# RGBstrip-ESP07-Controller-Amp.net
KiCad netlist of a schematic drawn in EAGLE
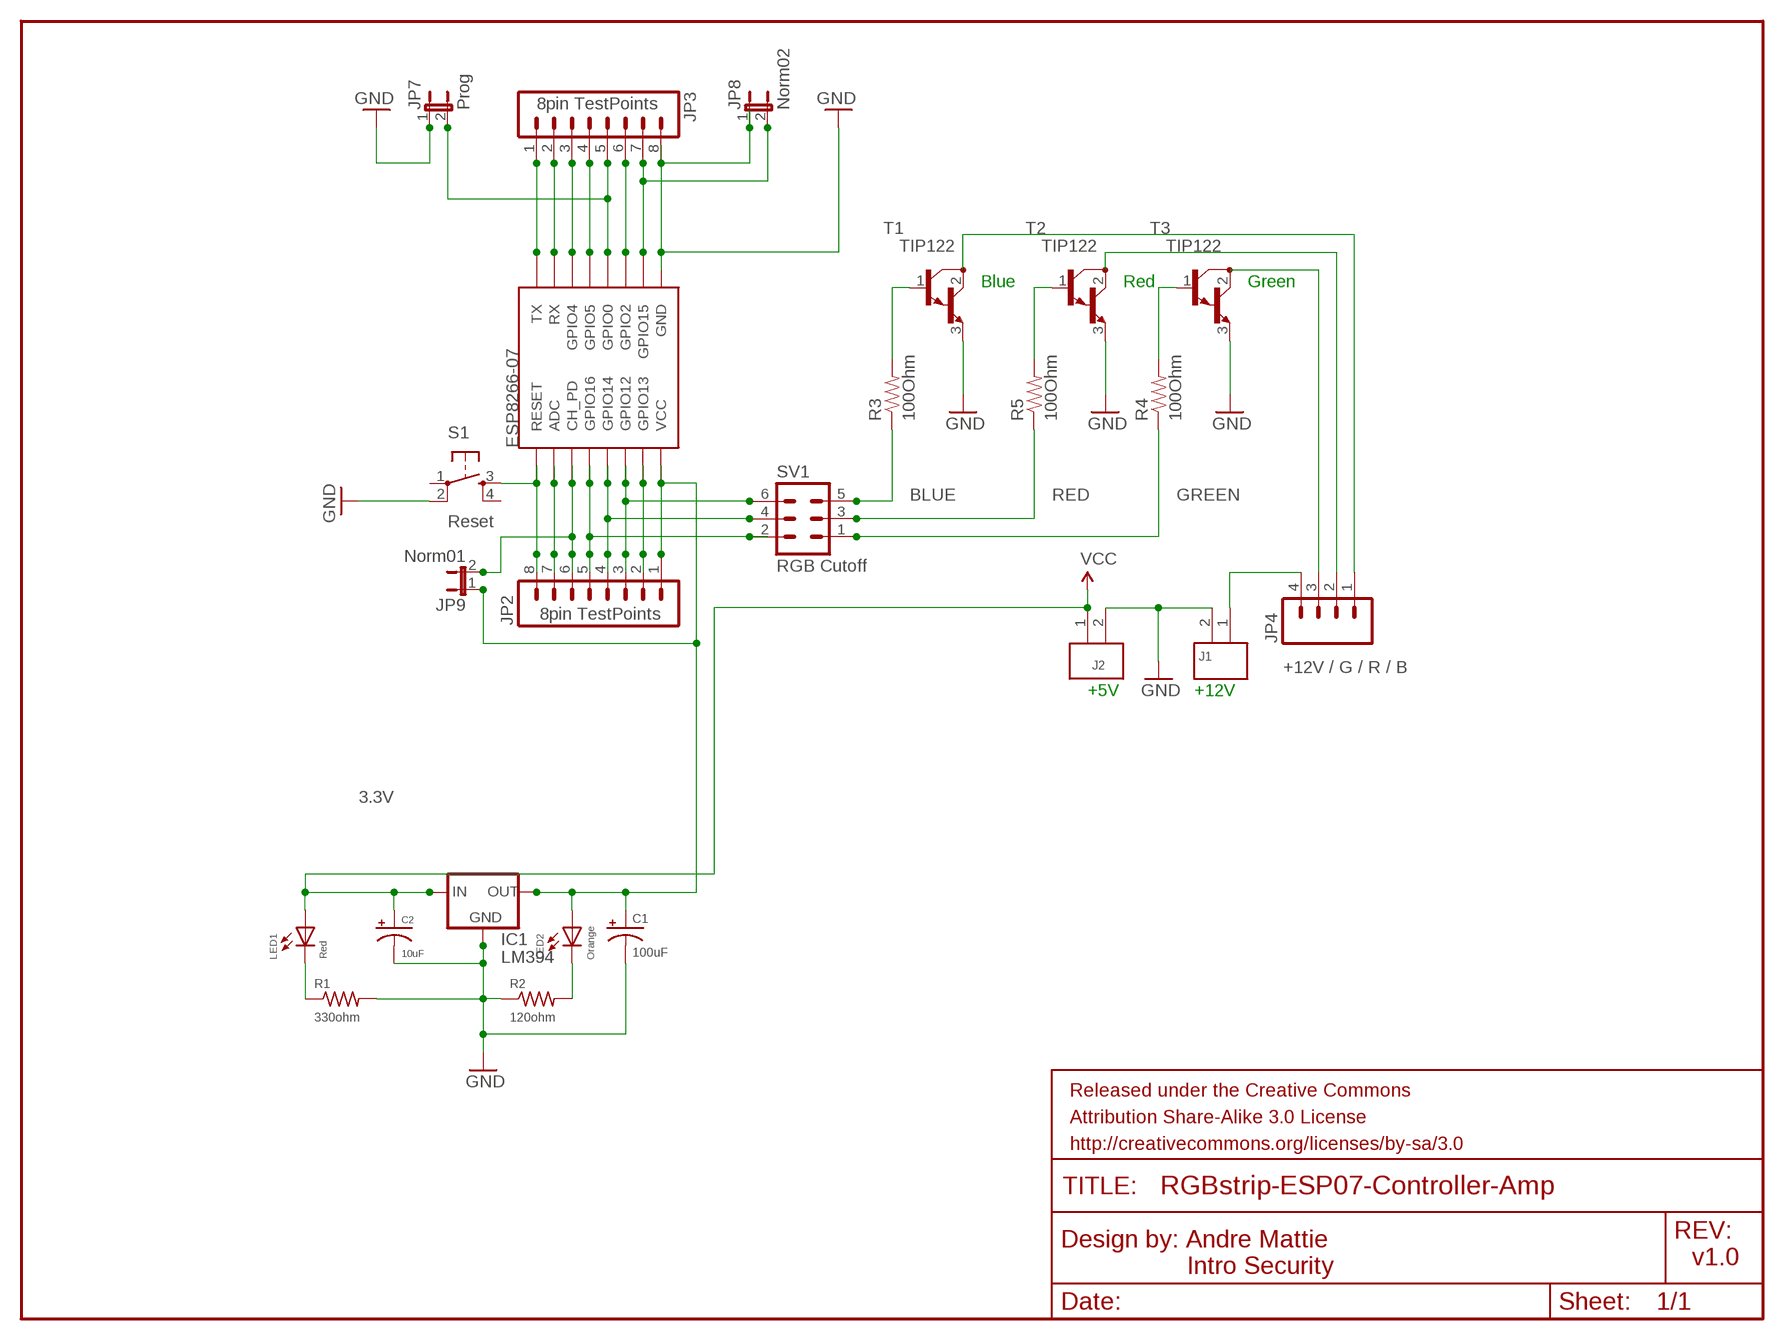
[diagram p0: schematic, sheet 1]

(export (version "E")
  (design (tool "Eeschema 10.0.6"))
  (components
    (comp (ref "C1")
      (value "100uF")
      (footprint "eagle-import:CPOL-RADIAL-100UF-25V")
      (libsource (lib "eagle-import") (part "CAP_POLPTH1"))
    )
    (comp (ref "C2")
      (value "10uF")
      (footprint "eagle-import:CPOL-RADIAL-10UF-25V")
      (libsource (lib "eagle-import") (part "CAP_POLPTH2"))
    )
    (comp (ref "ESP8266-07")
      (value "ESP07-16PIN")
      (footprint "eagle-import:ESP07-16PIN")
      (libsource (lib "eagle-import") (part "ESP07-16PIN"))
    )
    (comp (ref "FRAME1")
      (value "FRAME-LETTER")
      (footprint "eagle-import:CREATIVE_COMMONS")
      (libsource (lib "eagle-import") (part "FRAME-LETTER"))
    )
    (comp (ref "IC1")
      (value "LM394")
      (footprint "eagle-import:TO220-IGO")
      (libsource (lib "eagle-import") (part "V_REG_78XXSINK"))
    )
    (comp (ref "J1")
      (value "SCREW-TERMINAL_2_0.100")
      (footprint "eagle-import:CONN_BLOCK_2")
      (libsource (lib "eagle-import") (part "SCREW-TERMINAL_2_0.100"))
    )
    (comp (ref "J2")
      (value "SCREW-TERMINAL_2_0.100")
      (footprint "eagle-import:CONN_BLOCK_2")
      (libsource (lib "eagle-import") (part "SCREW-TERMINAL_2_0.100"))
    )
    (comp (ref "JP2")
      (value "8pin TestPoints")
      (footprint "eagle-import:1X08_LONGPADS")
      (libsource (lib "eagle-import") (part "M08LONGPADS"))
    )
    (comp (ref "JP3")
      (value "8pin TestPoints")
      (footprint "eagle-import:1X08_LONGPADS")
      (libsource (lib "eagle-import") (part "M08LONGPADS"))
    )
    (comp (ref "JP4")
      (value "+12V / G / R / B")
      (footprint "eagle-import:1X04_LONGPADS")
      (libsource (lib "eagle-import") (part "M04LONGPADS"))
    )
    (comp (ref "JP7")
      (value "Prog")
      (footprint "eagle-import:JP1")
      (libsource (lib "eagle-import") (part "JP1E"))
    )
    (comp (ref "JP8")
      (value "Norm02")
      (footprint "eagle-import:JP1")
      (libsource (lib "eagle-import") (part "JP1E"))
    )
    (comp (ref "JP9")
      (value "Norm01")
      (footprint "eagle-import:JP1")
      (libsource (lib "eagle-import") (part "JP1E"))
    )
    (comp (ref "LED1")
      (value "Red")
      (footprint "eagle-import:LED3MM")
      (libsource (lib "eagle-import") (part "LED3MM"))
    )
    (comp (ref "LED2")
      (value "Orange")
      (footprint "eagle-import:LED3MM")
      (libsource (lib "eagle-import") (part "LED3MM"))
    )
    (comp (ref "R1")
      (value "330ohm")
      (footprint "eagle-import:0309V")
      (libsource (lib "eagle-import") (part "R-US_0309/V"))
    )
    (comp (ref "R2")
      (value "120ohm")
      (footprint "eagle-import:0309V")
      (libsource (lib "eagle-import") (part "R-US_0309/V"))
    )
    (comp (ref "R3")
      (value "100Ohm")
      (footprint "eagle-import:AXIAL-0.4")
      (libsource (lib "eagle-import") (part "RESISTORPTH-1/4W"))
    )
    (comp (ref "R4")
      (value "100Ohm")
      (footprint "eagle-import:AXIAL-0.4")
      (libsource (lib "eagle-import") (part "RESISTORPTH-1/4W"))
    )
    (comp (ref "R5")
      (value "100Ohm")
      (footprint "eagle-import:AXIAL-0.4")
      (libsource (lib "eagle-import") (part "RESISTORPTH-1/4W"))
    )
    (comp (ref "S1")
      (value "Reset")
      (footprint "eagle-import:TACTILE-PTH")
      (libsource (lib "eagle-import") (part "TAC_SWITCHPTH"))
    )
    (comp (ref "SV1")
      (value "RGB Cutoff")
      (footprint "eagle-import:MA03-2")
      (libsource (lib "eagle-import") (part "MA03-2"))
    )
    (comp (ref "T1")
      (value "TIP122")
      (footprint "eagle-import:TO220")
      (libsource (lib "eagle-import") (part "TIP122"))
    )
    (comp (ref "T2")
      (value "TIP122")
      (footprint "eagle-import:TO220")
      (libsource (lib "eagle-import") (part "TIP122"))
    )
    (comp (ref "T3")
      (value "TIP122")
      (footprint "eagle-import:TO220")
      (libsource (lib "eagle-import") (part "TIP122"))
    )
  )
  (nets
    (net (code "1") (name "/3.3V") (class "Default")
      (node (ref "C1") (pin "1") (pinfunction "+_1") (pintype "passive"))
      (node (ref "ESP8266-07") (pin "VCC") (pinfunction "VCC_VCC") (pintype "bidirectional"))
      (node (ref "IC1") (pin "OUT") (pinfunction "OUT_OUT") (pintype "output"))
      (node (ref "JP2") (pin "1") (pinfunction "1_1") (pintype "passive"))
      (node (ref "JP9") (pin "1") (pinfunction "1_1") (pintype "passive"))
      (node (ref "LED2") (pin "A") (pinfunction "A_A") (pintype "passive"))
    )
    (net (code "2") (name "/BLUE") (class "Default")
      (node (ref "R3") (pin "P$1") (pinfunction "1_P$1") (pintype "passive"))
      (node (ref "SV1") (pin "5") (pinfunction "5_5") (pintype "passive"))
    )
    (net (code "3") (name "/GREEN") (class "Default")
      (node (ref "R4") (pin "P$1") (pinfunction "1_P$1") (pintype "passive"))
      (node (ref "SV1") (pin "1") (pinfunction "1_1") (pintype "passive"))
    )
    (net (code "4") (name "/RED") (class "Default")
      (node (ref "R5") (pin "P$1") (pinfunction "1_P$1") (pintype "passive"))
      (node (ref "SV1") (pin "3") (pinfunction "3_3") (pintype "passive"))
    )
    (net (code "5") (name "GND") (class "Default")
      (node (ref "C1") (pin "2") (pinfunction "-_2") (pintype "passive"))
      (node (ref "C2") (pin "2") (pinfunction "-_2") (pintype "passive"))
      (node (ref "ESP8266-07") (pin "GND") (pinfunction "GND_GND") (pintype "bidirectional"))
      (node (ref "IC1") (pin "GND") (pinfunction "GND_GND") (pintype "input"))
      (node (ref "J1") (pin "2") (pinfunction "2_2") (pintype "bidirectional"))
      (node (ref "J2") (pin "2") (pinfunction "2_2") (pintype "bidirectional"))
      (node (ref "JP3") (pin "8") (pinfunction "8_8") (pintype "passive"))
      (node (ref "JP7") (pin "1") (pinfunction "1_1") (pintype "passive"))
      (node (ref "JP8") (pin "1") (pinfunction "1_1") (pintype "passive"))
      (node (ref "R1") (pin "2") (pinfunction "2_2") (pintype "passive"))
      (node (ref "R2") (pin "1") (pinfunction "1_1") (pintype "passive"))
      (node (ref "S1") (pin "2") (pinfunction "2_2") (pintype "passive"))
      (node (ref "T1") (pin "3") (pinfunction "E_3") (pintype "passive"))
      (node (ref "T2") (pin "3") (pinfunction "E_3") (pintype "passive"))
      (node (ref "T3") (pin "3") (pinfunction "E_3") (pintype "passive"))
    )
    (net (code "6") (name "Net-(ESP8266-07-PadADC)") (class "Default")
      (node (ref "ESP8266-07") (pin "ADC") (pinfunction "ADC_ADC") (pintype "bidirectional"))
      (node (ref "JP2") (pin "7") (pinfunction "7_7") (pintype "passive"))
    )
    (net (code "7") (name "Net-(ESP8266-07-PadCH_PD)") (class "Default")
      (node (ref "ESP8266-07") (pin "CH_PD") (pinfunction "CH_PD_CH_PD") (pintype "bidirectional"))
      (node (ref "JP2") (pin "6") (pinfunction "6_6") (pintype "passive"))
      (node (ref "JP9") (pin "2") (pinfunction "2_2") (pintype "passive"))
    )
    (net (code "8") (name "Net-(ESP8266-07-PadGPIO0)") (class "Default")
      (node (ref "ESP8266-07") (pin "GPIO0") (pinfunction "GPIO0_GPIO0") (pintype "bidirectional"))
      (node (ref "JP3") (pin "5") (pinfunction "5_5") (pintype "passive"))
      (node (ref "JP7") (pin "2") (pinfunction "2_2") (pintype "passive"))
    )
    (net (code "9") (name "Net-(ESP8266-07-PadGPIO2)") (class "Default")
      (node (ref "ESP8266-07") (pin "GPIO2") (pinfunction "GPIO2_GPIO2") (pintype "bidirectional"))
      (node (ref "JP3") (pin "6") (pinfunction "6_6") (pintype "passive"))
    )
    (net (code "10") (name "Net-(ESP8266-07-PadGPIO4)") (class "Default")
      (node (ref "ESP8266-07") (pin "GPIO4") (pinfunction "GPIO4_GPIO4") (pintype "bidirectional"))
      (node (ref "JP3") (pin "3") (pinfunction "3_3") (pintype "passive"))
    )
    (net (code "11") (name "Net-(ESP8266-07-PadGPIO5)") (class "Default")
      (node (ref "ESP8266-07") (pin "GPIO5") (pinfunction "GPIO5_GPIO5") (pintype "bidirectional"))
      (node (ref "JP3") (pin "4") (pinfunction "4_4") (pintype "passive"))
    )
    (net (code "12") (name "Net-(ESP8266-07-PadGPIO12)") (class "Default")
      (node (ref "ESP8266-07") (pin "GPIO12") (pinfunction "GPIO12_GPIO12") (pintype "bidirectional"))
      (node (ref "JP2") (pin "3") (pinfunction "3_3") (pintype "passive"))
      (node (ref "SV1") (pin "6") (pinfunction "6_6") (pintype "passive"))
    )
    (net (code "13") (name "Net-(ESP8266-07-PadGPIO13)") (class "Default")
      (node (ref "ESP8266-07") (pin "GPIO13") (pinfunction "GPIO13_GPIO13") (pintype "bidirectional"))
      (node (ref "JP2") (pin "2") (pinfunction "2_2") (pintype "passive"))
    )
    (net (code "14") (name "Net-(ESP8266-07-PadGPIO14)") (class "Default")
      (node (ref "ESP8266-07") (pin "GPIO14") (pinfunction "GPIO14_GPIO14") (pintype "bidirectional"))
      (node (ref "JP2") (pin "4") (pinfunction "4_4") (pintype "passive"))
      (node (ref "SV1") (pin "4") (pinfunction "4_4") (pintype "passive"))
    )
    (net (code "15") (name "Net-(ESP8266-07-PadGPIO15)") (class "Default")
      (node (ref "ESP8266-07") (pin "GPIO15") (pinfunction "GPIO15_GPIO15") (pintype "bidirectional"))
      (node (ref "JP3") (pin "7") (pinfunction "7_7") (pintype "passive"))
      (node (ref "JP8") (pin "2") (pinfunction "2_2") (pintype "passive"))
    )
    (net (code "16") (name "Net-(ESP8266-07-PadGPIO16)") (class "Default")
      (node (ref "ESP8266-07") (pin "GPIO16") (pinfunction "GPIO16_GPIO16") (pintype "bidirectional"))
      (node (ref "JP2") (pin "5") (pinfunction "5_5") (pintype "passive"))
      (node (ref "SV1") (pin "2") (pinfunction "2_2") (pintype "passive"))
    )
    (net (code "17") (name "Net-(ESP8266-07-PadRX)") (class "Default")
      (node (ref "ESP8266-07") (pin "RX") (pinfunction "RX_RX") (pintype "bidirectional"))
      (node (ref "JP3") (pin "2") (pinfunction "2_2") (pintype "passive"))
    )
    (net (code "18") (name "Net-(ESP8266-07-PadTX)") (class "Default")
      (node (ref "ESP8266-07") (pin "TX") (pinfunction "TX_TX") (pintype "bidirectional"))
      (node (ref "JP3") (pin "1") (pinfunction "1_1") (pintype "passive"))
    )
    (net (code "19") (name "Net-(ESP8266-07-RESET)") (class "Default")
      (node (ref "ESP8266-07") (pin "REST") (pinfunction "RESET_REST") (pintype "bidirectional"))
      (node (ref "JP2") (pin "8") (pinfunction "8_8") (pintype "passive"))
      (node (ref "S1") (pin "3") (pinfunction "3_3") (pintype "passive"))
    )
    (net (code "20") (name "Net-(J1-Pad1)") (class "Default")
      (node (ref "J1") (pin "1") (pinfunction "1_1") (pintype "bidirectional"))
      (node (ref "JP4") (pin "4") (pinfunction "4_4") (pintype "passive"))
    )
    (net (code "21") (name "Net-(LED1-C)") (class "Default")
      (node (ref "LED1") (pin "K") (pinfunction "C_K") (pintype "passive"))
      (node (ref "R1") (pin "1") (pinfunction "1_1") (pintype "passive"))
    )
    (net (code "22") (name "Net-(LED2-C)") (class "Default")
      (node (ref "LED2") (pin "K") (pinfunction "C_K") (pintype "passive"))
      (node (ref "R2") (pin "2") (pinfunction "2_2") (pintype "passive"))
    )
    (net (code "23") (name "Net-(R3-2)") (class "Default")
      (node (ref "R3") (pin "P$2") (pinfunction "2_P$2") (pintype "passive"))
      (node (ref "T1") (pin "1") (pinfunction "B_1") (pintype "passive"))
    )
    (net (code "24") (name "Net-(R4-2)") (class "Default")
      (node (ref "R4") (pin "P$2") (pinfunction "2_P$2") (pintype "passive"))
      (node (ref "T3") (pin "1") (pinfunction "B_1") (pintype "passive"))
    )
    (net (code "25") (name "Net-(R5-2)") (class "Default")
      (node (ref "R5") (pin "P$2") (pinfunction "2_P$2") (pintype "passive"))
      (node (ref "T2") (pin "1") (pinfunction "B_1") (pintype "passive"))
    )
    (net (code "26") (name "Net-(T1-C)") (class "Default")
      (node (ref "JP4") (pin "1") (pinfunction "1_1") (pintype "passive"))
      (node (ref "T1") (pin "2") (pinfunction "C_2") (pintype "passive"))
    )
    (net (code "27") (name "Net-(T2-C)") (class "Default")
      (node (ref "JP4") (pin "2") (pinfunction "2_2") (pintype "passive"))
      (node (ref "T2") (pin "2") (pinfunction "C_2") (pintype "passive"))
    )
    (net (code "28") (name "Net-(T3-C)") (class "Default")
      (node (ref "JP4") (pin "3") (pinfunction "3_3") (pintype "passive"))
      (node (ref "T3") (pin "2") (pinfunction "C_2") (pintype "passive"))
    )
    (net (code "29") (name "VCC") (class "Default")
      (node (ref "C2") (pin "1") (pinfunction "+_1") (pintype "passive"))
      (node (ref "IC1") (pin "IN") (pinfunction "IN_IN") (pintype "input"))
      (node (ref "J2") (pin "1") (pinfunction "1_1") (pintype "bidirectional"))
      (node (ref "LED1") (pin "A") (pinfunction "A_A") (pintype "passive"))
    )
    (net (code "30") (name "unconnected-(S1-Pad1)") (class "Default")
      (node (ref "S1") (pin "1") (pinfunction "1_1") (pintype "passive"))
    )
    (net (code "31") (name "unconnected-(S1-Pad4)") (class "Default")
      (node (ref "S1") (pin "4") (pinfunction "4_4") (pintype "passive"))
    )
  )
)
